# MainBoard.net
KiCad netlist of a schematic drawn in Altium Designer
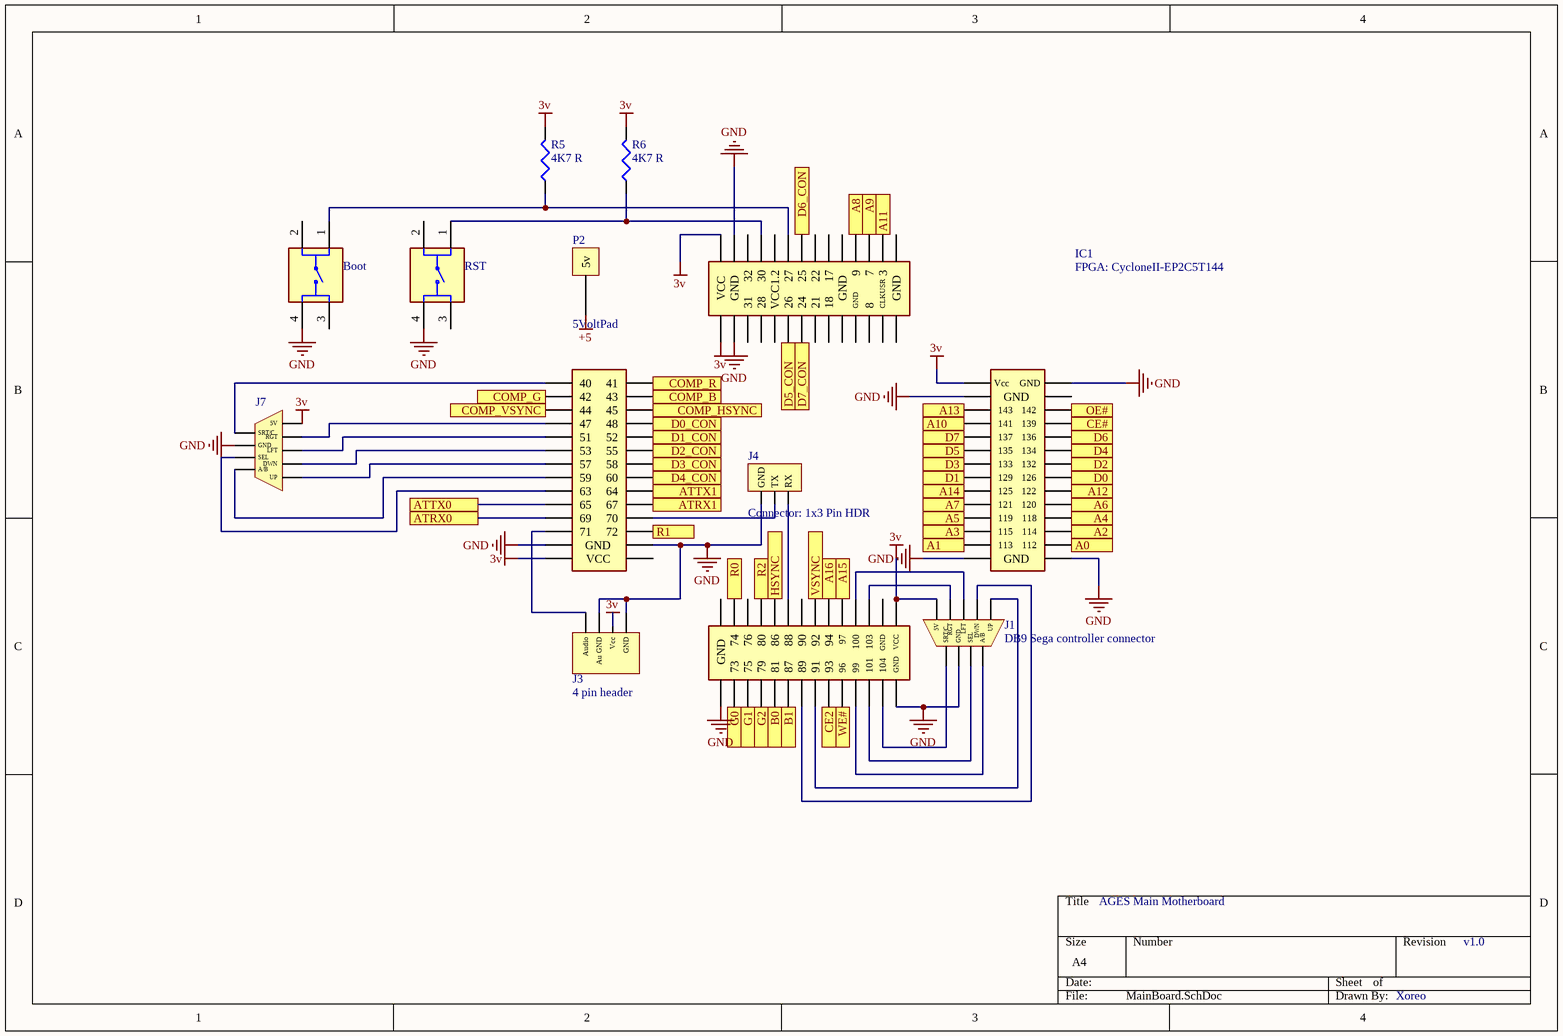
[diagram p0: MainBoard.SchDoc]

(export (version "E")
  (design (tool "Eeschema 10.0.6"))
  (components
    (comp (ref "Boot")
      (value "Button")
      (footprint "Button")
      (description "50 mA SPST Round Actuator 160 Gram Force Tactile Pushbutton Switch")
      (fields (field (name "MP") "1825910-2") (field (name "MF") "TE Connectivity"))
      (libsource (lib "Mobo") (part "Button"))
    )
    (comp (ref "IC1")
      (value "FPGA: CycloneII-EP2C5T144")
      (footprint "Cyclone II")
      (libsource (lib "Mobo") (part "FPGA{colon} CycloneII-EP2C5T144"))
    )
    (comp (ref "J1")
      (value "DB9 Sega controller connector")
      (footprint "DB9 Connector")
      (description "9 Way Right Angle Through Hole PCB D-sub Connector Socket; 2.77mm; 2.84mm Pitch")
      (fields
        (field (name "MANUFACTURER") "Wurth Electronics")
        (field (name "MANUFACTURER PART NUMBER") "618009231321")
      )
      (libsource (lib "Mobo") (part "Connector{colon} DB9"))
    )
    (comp (ref "J3")
      (value "4 pin header")
      (footprint "4 HDR")
      (description "Male 4 pin header")
      (libsource (lib "Mobo") (part "Connector{colon} 4 pin header"))
    )
    (comp (ref "J4")
      (value "Connector: 1x3 Pin HDR")
      (footprint "3 HDR")
      (libsource (lib "Mobo") (part "Connector{colon} 1x3 Pin HDR"))
    )
    (comp (ref "J7")
      (value "DB9 Sega controller connector")
      (footprint "DB9 Connector")
      (description "9 Way Right Angle Through Hole PCB D-sub Connector Socket; 2.77mm; 2.84mm Pitch")
      (fields
        (field (name "MANUFACTURER") "Wurth Electronics")
        (field (name "MANUFACTURER PART NUMBER") "618009231321")
      )
      (libsource (lib "Mobo") (part "Connector{colon} DB9"))
    )
    (comp (ref "P2") (value "5VoltPad") (footprint "5VoltPad") (libsource (lib "Mobo") (part "5VoltPad")))
    (comp (ref "R5")
      (value "4K7 R")
      (footprint "Resistor 0603")
      (description "Surface Mount Metal Film Resistor, Pcf Series, 4.7 Kohm, 63 Mw, - 0.1%, 75 V Rohs Compliant: Yes")
      (fields
        (field (name "MANUFACTURER") "TT Welwyn")
        (field (name "MANUFACTURER PART NUMBER") "PCF0603P-R-4K7-BT1")
      )
      (libsource (lib "Mobo") (part "Resistor{colon} 4K7"))
    )
    (comp (ref "R6")
      (value "4K7 R")
      (footprint "Resistor 0603")
      (description "Surface Mount Metal Film Resistor, Pcf Series, 4.7 Kohm, 63 Mw, - 0.1%, 75 V Rohs Compliant: Yes")
      (fields
        (field (name "MANUFACTURER") "TT Welwyn")
        (field (name "MANUFACTURER PART NUMBER") "PCF0603P-R-4K7-BT1")
      )
      (libsource (lib "Mobo") (part "Resistor{colon} 4K7"))
    )
    (comp (ref "RST")
      (value "Button")
      (footprint "Button")
      (description "50 mA SPST Round Actuator 160 Gram Force Tactile Pushbutton Switch")
      (fields (field (name "MP") "1825910-2") (field (name "MF") "TE Connectivity"))
      (libsource (lib "Mobo") (part "Button"))
    )
  )
  (nets
    (net (code "1") (name "+5") (class "Default")
      (node (ref "P2") (pin "1") (pinfunction "5v_1") (pintype "passive"))
    )
    (net (code "2") (name "/A0") (class "Default")
      (node (ref "IC1") (pin "109") (pinfunction "112_109") (pintype "passive"))
    )
    (net (code "3") (name "/A1") (class "Default")
      (node (ref "IC1") (pin "110") (pinfunction "113_110") (pintype "passive"))
    )
    (net (code "4") (name "/A2") (class "Default")
      (node (ref "IC1") (pin "107") (pinfunction "114_107") (pintype "passive"))
    )
    (net (code "5") (name "/A3") (class "Default")
      (node (ref "IC1") (pin "108") (pinfunction "115_108") (pintype "passive"))
    )
    (net (code "6") (name "/A4") (class "Default")
      (node (ref "IC1") (pin "105") (pinfunction "118_105") (pintype "passive"))
    )
    (net (code "7") (name "/A5") (class "Default")
      (node (ref "IC1") (pin "106") (pinfunction "119_106") (pintype "passive"))
    )
    (net (code "8") (name "/A6") (class "Default")
      (node (ref "IC1") (pin "103") (pinfunction "120_103") (pintype "passive"))
    )
    (net (code "9") (name "/A7") (class "Default")
      (node (ref "IC1") (pin "104") (pinfunction "121_104") (pintype "passive"))
    )
    (net (code "10") (name "/A8") (class "Default")
      (node (ref "IC1") (pin "7") (pinfunction "9_7") (pintype "passive"))
    )
    (net (code "11") (name "/A9") (class "Default")
      (node (ref "IC1") (pin "5") (pinfunction "7_5") (pintype "passive"))
    )
    (net (code "12") (name "/A10") (class "Default")
      (node (ref "IC1") (pin "92") (pinfunction "141_92") (pintype "passive"))
    )
    (net (code "13") (name "/A11") (class "Default")
      (node (ref "IC1") (pin "3") (pinfunction "3_3") (pintype "passive"))
    )
    (net (code "14") (name "/A12") (class "Default")
      (node (ref "IC1") (pin "101") (pinfunction "122_101") (pintype "passive"))
    )
    (net (code "15") (name "/A13") (class "Default")
      (node (ref "IC1") (pin "90") (pinfunction "143_90") (pintype "passive"))
    )
    (net (code "16") (name "/A14") (class "Default")
      (node (ref "IC1") (pin "102") (pinfunction "125_102") (pintype "passive"))
    )
    (net (code "17") (name "/A15") (class "Default")
      (node (ref "IC1") (pin "65") (pinfunction "97_65") (pintype "passive"))
    )
    (net (code "18") (name "/A16") (class "Default")
      (node (ref "IC1") (pin "67") (pinfunction "94_67") (pintype "passive"))
    )
    (net (code "19") (name "/ATRX0") (class "Default")
      (node (ref "IC1") (pin "49") (pinfunction "69_49") (pintype "passive"))
    )
    (net (code "20") (name "/ATRX1") (class "Default")
      (node (ref "IC1") (pin "48") (pinfunction "67_48") (pintype "passive"))
    )
    (net (code "21") (name "/ATTX0") (class "Default")
      (node (ref "IC1") (pin "47") (pinfunction "65_47") (pintype "passive"))
    )
    (net (code "22") (name "/ATTX1") (class "Default")
      (node (ref "IC1") (pin "46") (pinfunction "64_46") (pintype "passive"))
    )
    (net (code "23") (name "/B0") (class "Default")
      (node (ref "IC1") (pin "76") (pinfunction "81_76") (pintype "passive"))
    )
    (net (code "24") (name "/B1") (class "Default")
      (node (ref "IC1") (pin "74") (pinfunction "87_74") (pintype "passive"))
    )
    (net (code "25") (name "/CE#") (class "Default")
      (node (ref "IC1") (pin "91") (pinfunction "139_91") (pintype "passive"))
    )
    (net (code "26") (name "/CE2") (class "Default")
      (node (ref "IC1") (pin "68") (pinfunction "93_68") (pintype "passive"))
    )
    (net (code "27") (name "/COMP_B") (class "Default")
      (node (ref "IC1") (pin "32") (pinfunction "43_32") (pintype "passive"))
    )
    (net (code "28") (name "/COMP_G") (class "Default")
      (node (ref "IC1") (pin "31") (pinfunction "42_31") (pintype "passive"))
    )
    (net (code "29") (name "/COMP_HSYNC") (class "Default")
      (node (ref "IC1") (pin "34") (pinfunction "45_34") (pintype "passive"))
    )
    (net (code "30") (name "/COMP_R") (class "Default")
      (node (ref "IC1") (pin "30") (pinfunction "41_30") (pintype "passive"))
    )
    (net (code "31") (name "/COMP_VSYNC") (class "Default")
      (node (ref "IC1") (pin "33") (pinfunction "44_33") (pintype "passive"))
    )
    (net (code "32") (name "/D0") (class "Default")
      (node (ref "IC1") (pin "99") (pinfunction "126_99") (pintype "passive"))
    )
    (net (code "33") (name "/D0_CON") (class "Default")
      (node (ref "IC1") (pin "36") (pinfunction "48_36") (pintype "passive"))
    )
    (net (code "34") (name "/D1") (class "Default")
      (node (ref "IC1") (pin "100") (pinfunction "129_100") (pintype "passive"))
    )
    (net (code "35") (name "/D1_CON") (class "Default")
      (node (ref "IC1") (pin "38") (pinfunction "52_38") (pintype "passive"))
    )
    (net (code "36") (name "/D2") (class "Default")
      (node (ref "IC1") (pin "97") (pinfunction "132_97") (pintype "passive"))
    )
    (net (code "37") (name "/D2_CON") (class "Default")
      (node (ref "IC1") (pin "40") (pinfunction "55_40") (pintype "passive"))
    )
    (net (code "38") (name "/D3") (class "Default")
      (node (ref "IC1") (pin "98") (pinfunction "133_98") (pintype "passive"))
    )
    (net (code "39") (name "/D3_CON") (class "Default")
      (node (ref "IC1") (pin "42") (pinfunction "58_42") (pintype "passive"))
    )
    (net (code "40") (name "/D4") (class "Default")
      (node (ref "IC1") (pin "95") (pinfunction "134_95") (pintype "passive"))
    )
    (net (code "41") (name "/D4_CON") (class "Default")
      (node (ref "IC1") (pin "44") (pinfunction "60_44") (pintype "passive"))
    )
    (net (code "42") (name "/D5") (class "Default")
      (node (ref "IC1") (pin "96") (pinfunction "135_96") (pintype "passive"))
    )
    (net (code "43") (name "/D5_CON") (class "Default")
      (node (ref "IC1") (pin "18") (pinfunction "26_18") (pintype "passive"))
    )
    (net (code "44") (name "/D6") (class "Default")
      (node (ref "IC1") (pin "93") (pinfunction "136_93") (pintype "passive"))
    )
    (net (code "45") (name "/D6_CON") (class "Default")
      (node (ref "IC1") (pin "15") (pinfunction "25_15") (pintype "passive"))
    )
    (net (code "46") (name "/D7") (class "Default")
      (node (ref "IC1") (pin "94") (pinfunction "137_94") (pintype "passive"))
    )
    (net (code "47") (name "/D7_CON") (class "Default")
      (node (ref "IC1") (pin "16") (pinfunction "24_16") (pintype "passive"))
    )
    (net (code "48") (name "/G0") (class "Default")
      (node (ref "IC1") (pin "82") (pinfunction "73_82") (pintype "passive"))
    )
    (net (code "49") (name "/G1") (class "Default")
      (node (ref "IC1") (pin "80") (pinfunction "75_80") (pintype "passive"))
    )
    (net (code "50") (name "/G2") (class "Default")
      (node (ref "IC1") (pin "78") (pinfunction "79_78") (pintype "passive"))
    )
    (net (code "51") (name "/HSYNC") (class "Default")
      (node (ref "IC1") (pin "75") (pinfunction "86_75") (pintype "passive"))
    )
    (net (code "52") (name "/OE#") (class "Default")
      (node (ref "IC1") (pin "89") (pinfunction "142_89") (pintype "passive"))
    )
    (net (code "53") (name "/R0") (class "Default")
      (node (ref "IC1") (pin "81") (pinfunction "74_81") (pintype "passive"))
    )
    (net (code "54") (name "/R1") (class "Default")
      (node (ref "IC1") (pin "52") (pinfunction "72_52") (pintype "passive"))
    )
    (net (code "55") (name "/R2") (class "Default")
      (node (ref "IC1") (pin "77") (pinfunction "80_77") (pintype "passive"))
    )
    (net (code "56") (name "/VSYNC") (class "Default")
      (node (ref "IC1") (pin "69") (pinfunction "92_69") (pintype "passive"))
    )
    (net (code "57") (name "/WE#") (class "Default")
      (node (ref "IC1") (pin "66") (pinfunction "96_66") (pintype "passive"))
    )
    (net (code "58") (name "3v") (class "Default")
      (node (ref "IC1") (pin "27") (pinfunction "VCC_27") (pintype "passive"))
      (node (ref "IC1") (pin "28") (pinfunction "VCC_28") (pintype "passive"))
      (node (ref "IC1") (pin "55") (pinfunction "14_55") (pintype "passive"))
      (node (ref "IC1") (pin "57") (pinfunction "VCC_57") (pintype "passive"))
      (node (ref "IC1") (pin "86") (pinfunction "Vcc_86") (pintype "passive"))
      (node (ref "J1") (pin "5") (pinfunction "5V_5") (pintype "passive"))
      (node (ref "J3") (pin "2") (pinfunction "Vcc_2") (pintype "passive"))
      (node (ref "J7") (pin "5") (pinfunction "5V_5") (pintype "passive"))
      (node (ref "R5") (pin "2") (pinfunction "2_2") (pintype "passive"))
      (node (ref "R6") (pin "2") (pinfunction "2_2") (pintype "passive"))
    )
    (net (code "59") (name "GND") (class "Default")
      (node (ref "Boot") (pin "4") (pinfunction "4_4") (pintype "passive"))
      (node (ref "IC1") (pin "111") (pinfunction "GND_111") (pintype "passive"))
      (node (ref "IC1") (pin "112") (pinfunction "14_112") (pintype "passive"))
      (node (ref "IC1") (pin "25") (pinfunction "GND_25") (pintype "passive"))
      (node (ref "IC1") (pin "26") (pinfunction "GND_26") (pintype "passive"))
      (node (ref "IC1") (pin "53") (pinfunction "13_53") (pintype "passive"))
      (node (ref "IC1") (pin "54") (pinfunction "GND_54") (pintype "passive"))
      (node (ref "IC1") (pin "58") (pinfunction "GND_58") (pintype "passive"))
      (node (ref "IC1") (pin "84") (pinfunction "GND_84") (pintype "passive"))
      (node (ref "IC1") (pin "85") (pinfunction "GND_85") (pintype "passive"))
      (node (ref "IC1") (pin "88") (pinfunction "42_88") (pintype "passive"))
      (node (ref "J1") (pin "8") (pinfunction "GND_8") (pintype "passive"))
      (node (ref "J3") (pin "1") (pinfunction "GND_1") (pintype "passive"))
      (node (ref "J3") (pin "3") (pinfunction "Au_GND_3") (pintype "passive"))
      (node (ref "J4") (pin "1") (pinfunction "GND_1") (pintype "passive"))
      (node (ref "J7") (pin "8") (pinfunction "GND_8") (pintype "passive"))
      (node (ref "RST") (pin "4") (pinfunction "4_4") (pintype "passive"))
    )
    (net (code "60") (name "Net-(IC1-27)") (class "Default")
      (node (ref "Boot") (pin "1") (pinfunction "1_1") (pintype "passive"))
      (node (ref "IC1") (pin "17") (pinfunction "27_17") (pintype "passive"))
      (node (ref "R5") (pin "1") (pinfunction "1_1") (pintype "passive"))
    )
    (net (code "61") (name "Net-(IC1-30)") (class "Default")
      (node (ref "IC1") (pin "21") (pinfunction "30_21") (pintype "passive"))
      (node (ref "R6") (pin "1") (pinfunction "1_1") (pintype "passive"))
      (node (ref "RST") (pin "1") (pinfunction "1_1") (pintype "passive"))
    )
    (net (code "62") (name "Net-(IC1-40)") (class "Default")
      (node (ref "IC1") (pin "29") (pinfunction "40_29") (pintype "passive"))
      (node (ref "J7") (pin "9") (pinfunction "SRT/C_9") (pintype "passive"))
    )
    (net (code "63") (name "Net-(IC1-47)") (class "Default")
      (node (ref "IC1") (pin "35") (pinfunction "47_35") (pintype "passive"))
      (node (ref "J7") (pin "4") (pinfunction "RGT_4") (pintype "passive"))
    )
    (net (code "64") (name "Net-(IC1-51)") (class "Default")
      (node (ref "IC1") (pin "37") (pinfunction "51_37") (pintype "passive"))
      (node (ref "J7") (pin "3") (pinfunction "LFT_3") (pintype "passive"))
    )
    (net (code "65") (name "Net-(IC1-53)") (class "Default")
      (node (ref "IC1") (pin "39") (pinfunction "53_39") (pintype "passive"))
      (node (ref "J7") (pin "2") (pinfunction "DWN_2") (pintype "passive"))
    )
    (net (code "66") (name "Net-(IC1-57)") (class "Default")
      (node (ref "IC1") (pin "41") (pinfunction "57_41") (pintype "passive"))
      (node (ref "J7") (pin "1") (pinfunction "UP_1") (pintype "passive"))
    )
    (net (code "67") (name "Net-(IC1-59)") (class "Default")
      (node (ref "IC1") (pin "43") (pinfunction "59_43") (pintype "passive"))
      (node (ref "J7") (pin "6") (pinfunction "A/B_6") (pintype "passive"))
    )
    (net (code "68") (name "Net-(IC1-63)") (class "Default")
      (node (ref "IC1") (pin "45") (pinfunction "63_45") (pintype "passive"))
      (node (ref "J7") (pin "7") (pinfunction "SEL_7") (pintype "passive"))
    )
    (net (code "69") (name "Net-(IC1-70)") (class "Default")
      (node (ref "IC1") (pin "50") (pinfunction "70_50") (pintype "passive"))
      (node (ref "J4") (pin "2") (pinfunction "TX_2") (pintype "passive"))
    )
    (net (code "70") (name "Net-(IC1-71)") (class "Default")
      (node (ref "IC1") (pin "51") (pinfunction "71_51") (pintype "passive"))
      (node (ref "J3") (pin "4") (pinfunction "Audio_4") (pintype "passive"))
    )
    (net (code "71") (name "Net-(IC1-88)") (class "Default")
      (node (ref "IC1") (pin "73") (pinfunction "88_73") (pintype "passive"))
      (node (ref "J4") (pin "3") (pinfunction "RX_3") (pintype "passive"))
    )
    (net (code "72") (name "Net-(IC1-89)") (class "Default")
      (node (ref "IC1") (pin "72") (pinfunction "89_72") (pintype "passive"))
      (node (ref "J1") (pin "2") (pinfunction "DWN_2") (pintype "passive"))
    )
    (net (code "73") (name "Net-(IC1-91)") (class "Default")
      (node (ref "IC1") (pin "70") (pinfunction "91_70") (pintype "passive"))
      (node (ref "J1") (pin "1") (pinfunction "UP_1") (pintype "passive"))
    )
    (net (code "74") (name "Net-(IC1-99)") (class "Default")
      (node (ref "IC1") (pin "64") (pinfunction "99_64") (pintype "passive"))
      (node (ref "J1") (pin "6") (pinfunction "A/B_6") (pintype "passive"))
    )
    (net (code "75") (name "Net-(IC1-100)") (class "Default")
      (node (ref "IC1") (pin "63") (pinfunction "100_63") (pintype "passive"))
      (node (ref "J1") (pin "3") (pinfunction "LFT_3") (pintype "passive"))
    )
    (net (code "76") (name "Net-(IC1-101)") (class "Default")
      (node (ref "IC1") (pin "62") (pinfunction "101_62") (pintype "passive"))
      (node (ref "J1") (pin "7") (pinfunction "SEL_7") (pintype "passive"))
    )
    (net (code "77") (name "Net-(IC1-103)") (class "Default")
      (node (ref "IC1") (pin "61") (pinfunction "103_61") (pintype "passive"))
      (node (ref "J1") (pin "4") (pinfunction "RGT_4") (pintype "passive"))
    )
    (net (code "78") (name "Net-(IC1-104)") (class "Default")
      (node (ref "IC1") (pin "60") (pinfunction "104_60") (pintype "passive"))
      (node (ref "J1") (pin "9") (pinfunction "SRT/C_9") (pintype "passive"))
    )
    (net (code "79") (name "unconnected-(Boot-Pad2)") (class "Default")
      (node (ref "Boot") (pin "2") (pinfunction "2_2") (pintype "passive"))
    )
    (net (code "80") (name "unconnected-(Boot-Pad3)") (class "Default")
      (node (ref "Boot") (pin "3") (pinfunction "3_3") (pintype "passive"))
    )
    (net (code "81") (name "unconnected-(IC1-8-Pad6)") (class "Default")
      (node (ref "IC1") (pin "6") (pinfunction "8_6") (pintype "passive"))
    )
    (net (code "82") (name "unconnected-(IC1-17-Pad11)") (class "Default")
      (node (ref "IC1") (pin "11") (pinfunction "17_11") (pintype "passive"))
    )
    (net (code "83") (name "unconnected-(IC1-18-Pad12)") (class "Default")
      (node (ref "IC1") (pin "12") (pinfunction "18_12") (pintype "passive"))
    )
    (net (code "84") (name "unconnected-(IC1-21-Pad14)") (class "Default")
      (node (ref "IC1") (pin "14") (pinfunction "21_14") (pintype "passive"))
    )
    (net (code "85") (name "unconnected-(IC1-22-Pad13)") (class "Default")
      (node (ref "IC1") (pin "13") (pinfunction "22_13") (pintype "passive"))
    )
    (net (code "86") (name "unconnected-(IC1-28-Pad22)") (class "Default")
      (node (ref "IC1") (pin "22") (pinfunction "28_22") (pintype "passive"))
    )
    (net (code "87") (name "unconnected-(IC1-31-Pad24)") (class "Default")
      (node (ref "IC1") (pin "24") (pinfunction "31_24") (pintype "passive"))
    )
    (net (code "88") (name "unconnected-(IC1-32-Pad23)") (class "Default")
      (node (ref "IC1") (pin "23") (pinfunction "32_23") (pintype "passive"))
    )
    (net (code "89") (name "unconnected-(IC1-76-Pad79)") (class "Default")
      (node (ref "IC1") (pin "79") (pinfunction "76_79") (pintype "passive"))
    )
    (net (code "90") (name "unconnected-(IC1-90-Pad71)") (class "Default")
      (node (ref "IC1") (pin "71") (pinfunction "90_71") (pintype "passive"))
    )
    (net (code "91") (name "unconnected-(IC1-CLKUSR-Pad4)") (class "Default")
      (node (ref "IC1") (pin "4") (pinfunction "CLKUSR_4") (pintype "passive"))
    )
    (net (code "92") (name "unconnected-(IC1-GND-Pad1)") (class "Default")
      (node (ref "IC1") (pin "1") (pinfunction "GND_1") (pintype "passive"))
    )
    (net (code "93") (name "unconnected-(IC1-GND-Pad2)") (class "Default")
      (node (ref "IC1") (pin "2") (pinfunction "GND_2") (pintype "passive"))
    )
    (net (code "94") (name "unconnected-(IC1-GND-Pad8)") (class "Default")
      (node (ref "IC1") (pin "8") (pinfunction "GND_8") (pintype "passive"))
    )
    (net (code "95") (name "unconnected-(IC1-GND-Pad9)") (class "Default")
      (node (ref "IC1") (pin "9") (pinfunction "GND_9") (pintype "passive"))
    )
    (net (code "96") (name "unconnected-(IC1-GND-Pad10)") (class "Default")
      (node (ref "IC1") (pin "10") (pinfunction "GND_10") (pintype "passive"))
    )
    (net (code "97") (name "unconnected-(IC1-GND-Pad59)") (class "Default")
      (node (ref "IC1") (pin "59") (pinfunction "GND_59") (pintype "passive"))
    )
    (net (code "98") (name "unconnected-(IC1-GND-Pad87)") (class "Default")
      (node (ref "IC1") (pin "87") (pinfunction "GND_87") (pintype "passive"))
    )
    (net (code "99") (name "unconnected-(IC1-VCC-Pad56)") (class "Default")
      (node (ref "IC1") (pin "56") (pinfunction "VCC_56") (pintype "passive"))
    )
    (net (code "100") (name "unconnected-(IC1-VCC-Pad83)") (class "Default")
      (node (ref "IC1") (pin "83") (pinfunction "VCC_83") (pintype "passive"))
    )
    (net (code "101") (name "unconnected-(IC1-VCC1.2-Pad19)") (class "Default")
      (node (ref "IC1") (pin "19") (pinfunction "VCC1.2_19") (pintype "passive"))
    )
    (net (code "102") (name "unconnected-(IC1-VCC1.2-Pad20)") (class "Default")
      (node (ref "IC1") (pin "20") (pinfunction "VCC1.2_20") (pintype "passive"))
    )
    (net (code "103") (name "unconnected-(RST-Pad2)") (class "Default")
      (node (ref "RST") (pin "2") (pinfunction "2_2") (pintype "passive"))
    )
    (net (code "104") (name "unconnected-(RST-Pad3)") (class "Default")
      (node (ref "RST") (pin "3") (pinfunction "3_3") (pintype "passive"))
    )
  )
)
